# ST_Sensor_Output_Socket.net
KiCad netlist of a schematic drawn in Altium Designer
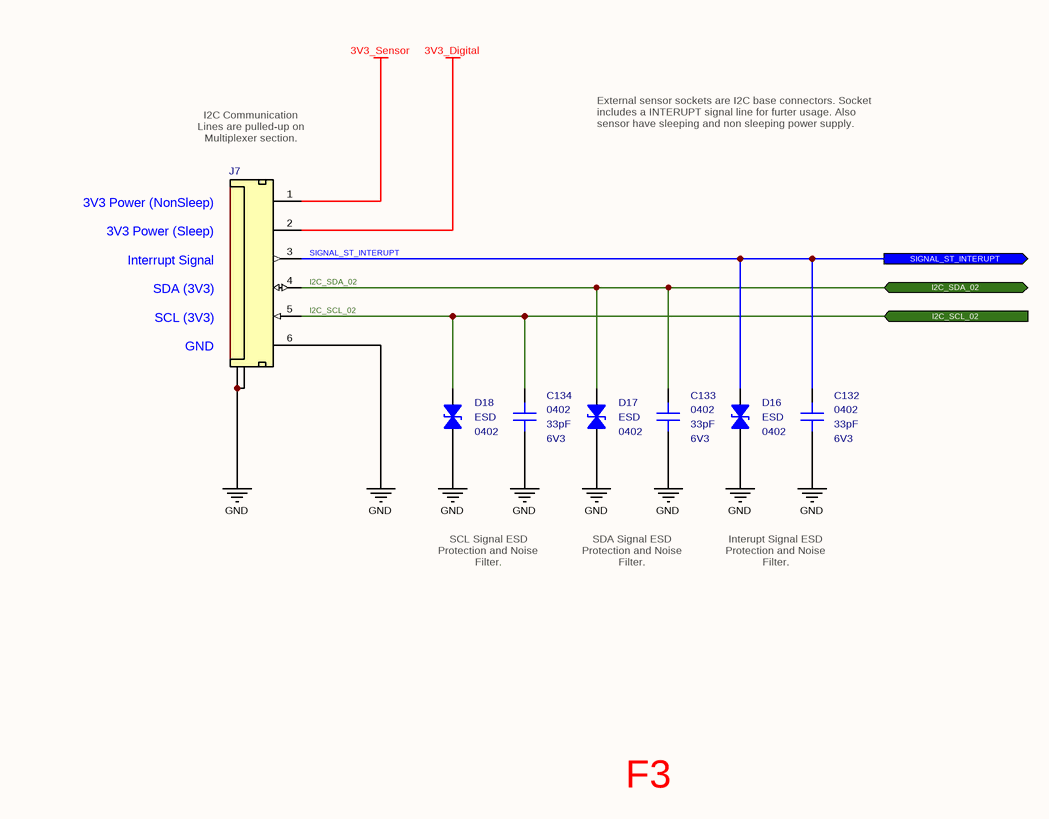
[diagram p0: ST Sensor Output Socket.SchDoc]

(export (version "E")
  (design (tool "Eeschema 10.0.6"))
  (components
    (comp (ref "C132")
      (value "33pF")
      (footprint "CAPACITOR_0402")
      (description "Capacitor - 33pF [0402] (Ceramic)")
      (fields
        (field (name "MANUFACTURER_PART_NUMBER") "C0402C330J9RACAUTO")
        (field (name "MOUSER_PART_NUMBER") "80-C0402C330J9RAUTO")
        (field (name "CASE") "0402")
        (field (name "VOLTAGE") "6V3")
      )
      (libsource (lib "Ovoo_Schematic") (part "Capacitor - 33pF [0402-6V3]"))
    )
    (comp (ref "C133")
      (value "33pF")
      (footprint "CAPACITOR_0402")
      (description "Capacitor - 33pF [0402] (Ceramic)")
      (fields
        (field (name "MANUFACTURER_PART_NUMBER") "C0402C330J9RACAUTO")
        (field (name "MOUSER_PART_NUMBER") "80-C0402C330J9RAUTO")
        (field (name "CASE") "0402")
        (field (name "VOLTAGE") "6V3")
      )
      (libsource (lib "Ovoo_Schematic") (part "Capacitor - 33pF [0402-6V3]"))
    )
    (comp (ref "C134")
      (value "33pF")
      (footprint "CAPACITOR_0402")
      (description "Capacitor - 33pF [0402] (Ceramic)")
      (fields
        (field (name "MANUFACTURER_PART_NUMBER") "C0402C330J9RACAUTO")
        (field (name "MOUSER_PART_NUMBER") "80-C0402C330J9RAUTO")
        (field (name "CASE") "0402")
        (field (name "VOLTAGE") "6V3")
      )
      (libsource (lib "Ovoo_Schematic") (part "Capacitor - 33pF [0402-6V3]"))
    )
    (comp (ref "D16")
      (value "ESD Suppressors")
      (footprint "ESD_0402")
      (description "TVS Diode (Bi-directional)")
      (fields
        (field (name "MANUFACTURER_PART_NUMBER") "0402ESDA-MLP1")
        (field (name "MOUSER_PART_NUMBER") "504-0402ESDA-MLP1")
        (field (name "CASE") "0402")
      )
      (libsource (lib "Ovoo_Schematic") (part "Diode - ESD Protection"))
    )
    (comp (ref "D17")
      (value "ESD Suppressors")
      (footprint "ESD_0402")
      (description "TVS Diode (Bi-directional)")
      (fields
        (field (name "MANUFACTURER_PART_NUMBER") "0402ESDA-MLP1")
        (field (name "MOUSER_PART_NUMBER") "504-0402ESDA-MLP1")
        (field (name "CASE") "0402")
      )
      (libsource (lib "Ovoo_Schematic") (part "Diode - ESD Protection"))
    )
    (comp (ref "D18")
      (value "ESD Suppressors")
      (footprint "ESD_0402")
      (description "TVS Diode (Bi-directional)")
      (fields
        (field (name "MANUFACTURER_PART_NUMBER") "0402ESDA-MLP1")
        (field (name "MOUSER_PART_NUMBER") "504-0402ESDA-MLP1")
        (field (name "CASE") "0402")
      )
      (libsource (lib "Ovoo_Schematic") (part "Diode - ESD Protection"))
    )
    (comp (ref "J7")
      (value "ST Sensor Socket")
      (footprint "Connector_Tunic 6P - H")
      (description "Mini Tunic Connector with 6P")
      (fields (field (name "MANUFACTURER_PART_NUMBER") "53261-0671"))
      (libsource (lib "Ovoo_Schematic") (part "Connector - Mini Tunic 6P (1.25)"))
    )
  )
  (nets
    (net (code "1") (name "/I2C_SCL_02") (class "Default")
      (node (ref "C134") (pin "2") (pinfunction "2_2") (pintype "passive"))
      (node (ref "D18") (pin "2") (pinfunction "2_2") (pintype "passive"))
      (node (ref "J7") (pin "5") (pinfunction "SCL02_5") (pintype "input"))
    )
    (net (code "2") (name "/I2C_SDA_02") (class "Default")
      (node (ref "C133") (pin "2") (pinfunction "2_2") (pintype "passive"))
      (node (ref "D17") (pin "2") (pinfunction "2_2") (pintype "passive"))
      (node (ref "J7") (pin "4") (pinfunction "SDA02_4") (pintype "bidirectional"))
    )
    (net (code "3") (name "/SIGNAL_ST_INTERUPT") (class "Default")
      (node (ref "C132") (pin "2") (pinfunction "2_2") (pintype "passive"))
      (node (ref "D16") (pin "2") (pinfunction "2_2") (pintype "passive"))
      (node (ref "J7") (pin "3") (pinfunction "ST_Interupt_3") (pintype "output"))
    )
    (net (code "4") (name "3V3_Digital") (class "Default")
      (node (ref "J7") (pin "2") (pinfunction "3V3_Digital_2") (pintype "power_in"))
    )
    (net (code "5") (name "3V3_Sensor") (class "Default")
      (node (ref "J7") (pin "1") (pinfunction "3V3_Sensor_1") (pintype "power_in"))
    )
    (net (code "6") (name "GND") (class "Default")
      (node (ref "C132") (pin "1") (pinfunction "1_1") (pintype "passive"))
      (node (ref "C133") (pin "1") (pinfunction "1_1") (pintype "passive"))
      (node (ref "C134") (pin "1") (pinfunction "1_1") (pintype "passive"))
      (node (ref "D16") (pin "1") (pinfunction "1_1") (pintype "passive"))
      (node (ref "D17") (pin "1") (pinfunction "1_1") (pintype "passive"))
      (node (ref "D18") (pin "1") (pinfunction "1_1") (pintype "passive"))
      (node (ref "J7") (pin "6") (pinfunction "GND_6") (pintype "power_in"))
      (node (ref "J7") (pin "7") (pinfunction "Termination_7") (pintype "passive"))
      (node (ref "J7") (pin "8") (pinfunction "Termination_8") (pintype "passive"))
    )
  )
)
